# nrf24l01_shield.net
KiCad netlist of a schematic drawn in EAGLE
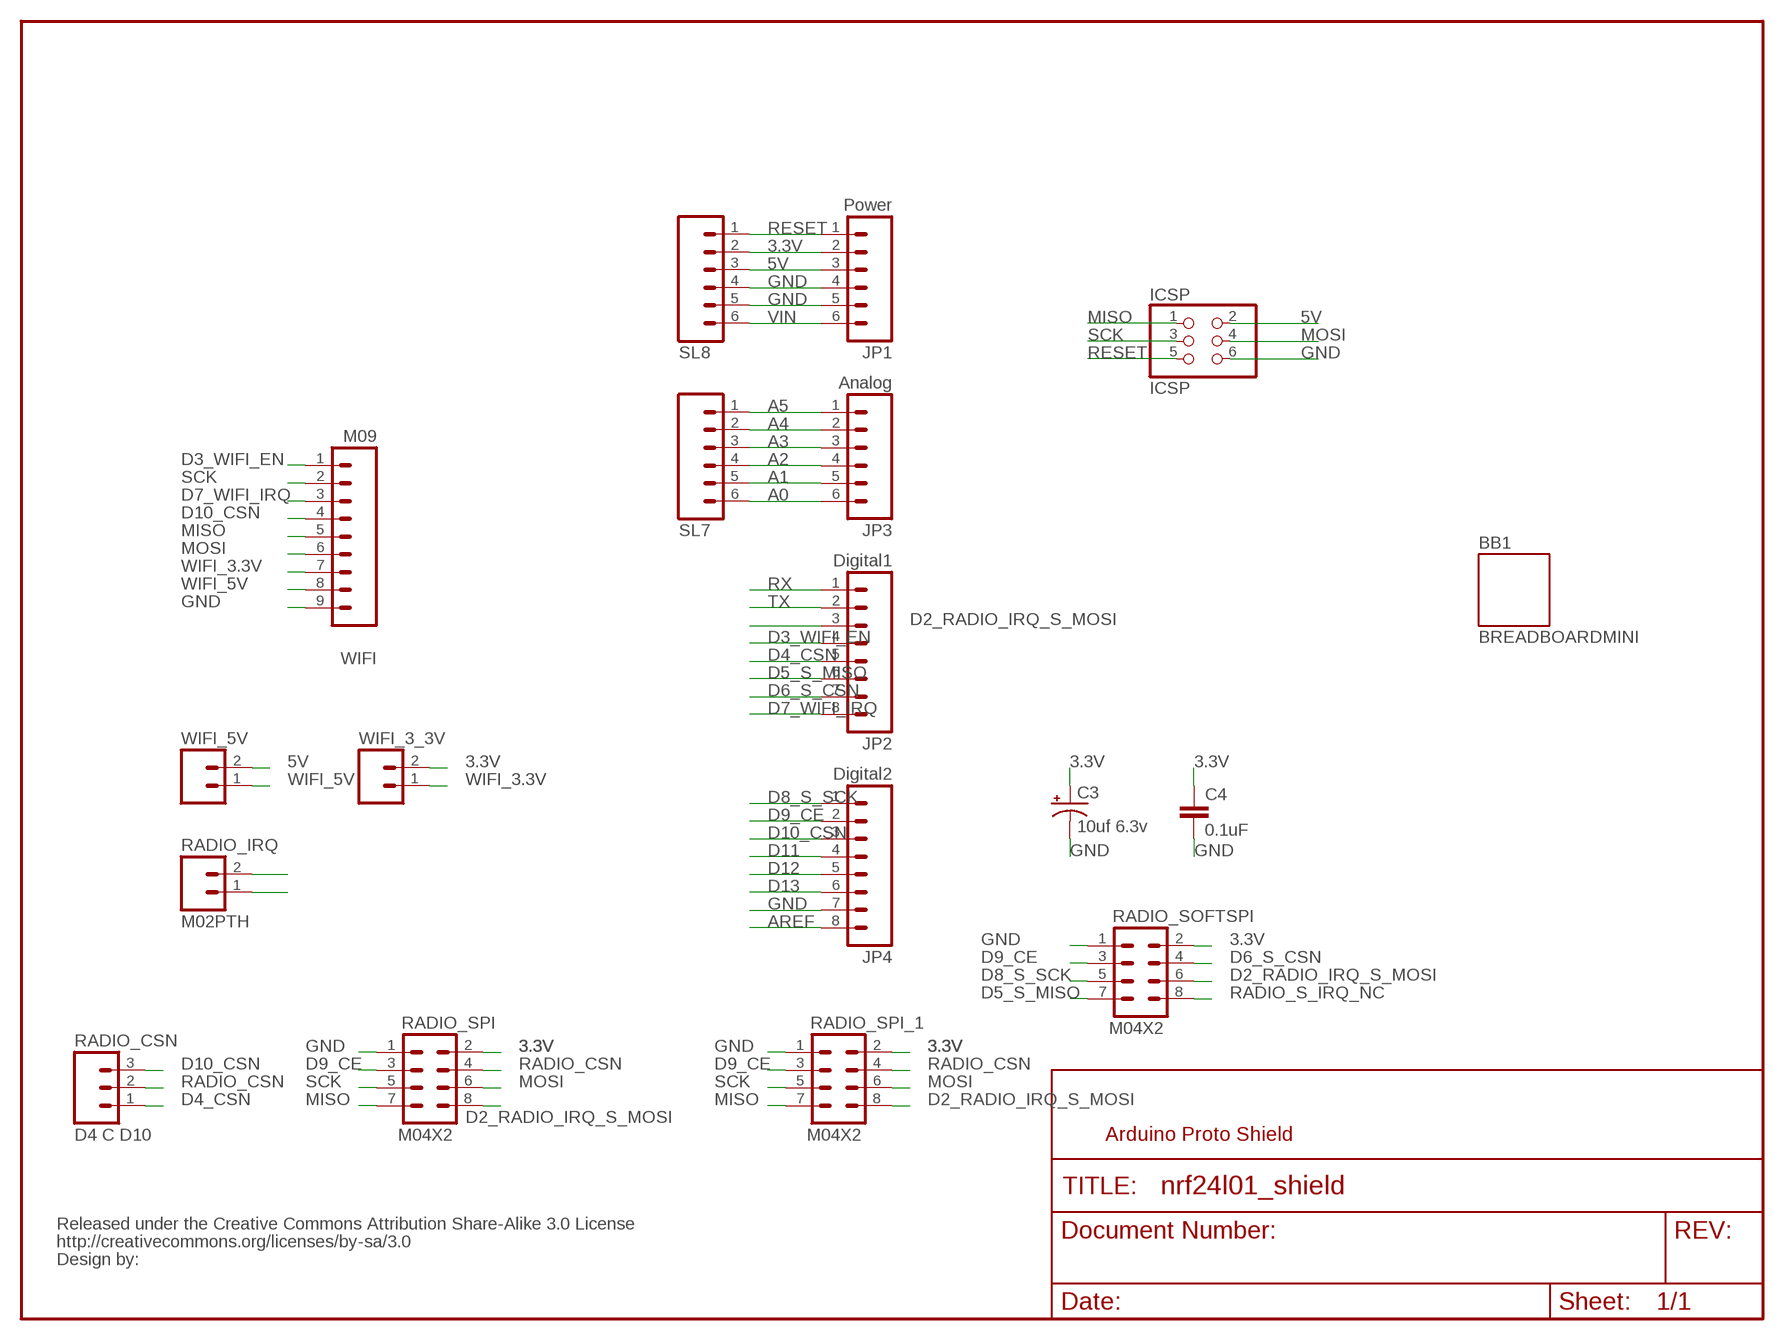
[diagram p0: schematic, sheet 1]

(export (version "E")
  (design (tool "Eeschema 10.0.6"))
  (components
    (comp (ref "BB1")
      (value "BREADBOARDMINI")
      (footprint "eagle-import:BREADBOARD-MINI")
      (libsource (lib "eagle-import") (part "BREADBOARDMINI"))
    )
    (comp (ref "C3")
      (value "10uf 6.3v")
      (footprint "eagle-import:CPOL-RADIAL-10UF-25V")
      (libsource (lib "eagle-import") (part "CAP_POLPTH2"))
    )
    (comp (ref "C4")
      (value "0.1uF")
      (footprint "eagle-import:CAP-PTH-SMALL2")
      (libsource (lib "eagle-import") (part "CAPPTH2"))
    )
    (comp (ref "ICSP")
      (value "ICSP")
      (footprint "eagle-import:2X03")
      (libsource (lib "eagle-import") (part "PINHD-2X3"))
    )
    (comp (ref "JP1")
      (value "Power")
      (footprint "eagle-import:1X06")
      (libsource (lib "eagle-import") (part "M06SIP"))
    )
    (comp (ref "JP2")
      (value "Digital1")
      (footprint "eagle-import:1X08")
      (libsource (lib "eagle-import") (part "M08"))
    )
    (comp (ref "JP3")
      (value "Analog")
      (footprint "eagle-import:1X06")
      (libsource (lib "eagle-import") (part "M06SIP"))
    )
    (comp (ref "JP4")
      (value "Digital2")
      (footprint "eagle-import:1X08")
      (libsource (lib "eagle-import") (part "M08"))
    )
    (comp (ref "RADIO_CSN")
      (value "D4 C D10")
      (footprint "eagle-import:1X03")
      (libsource (lib "eagle-import") (part "M03PTH"))
    )
    (comp (ref "RADIO_IRQ")
      (value "M02PTH")
      (footprint "eagle-import:1X02")
      (libsource (lib "eagle-import") (part "M02PTH"))
    )
    (comp (ref "RADIO_SOFTSPI")
      (value "M04X2")
      (footprint "eagle-import:2X4")
      (libsource (lib "eagle-import") (part "M04X2"))
    )
    (comp (ref "RADIO_SPI")
      (value "M04X2")
      (footprint "eagle-import:2X4")
      (libsource (lib "eagle-import") (part "M04X2"))
    )
    (comp (ref "RADIO_SPI_1")
      (value "M04X2")
      (footprint "eagle-import:2X4")
      (libsource (lib "eagle-import") (part "M04X2"))
    )
    (comp (ref "SL7")
      (value "M06SIP")
      (footprint "eagle-import:1X06")
      (libsource (lib "eagle-import") (part "M06SIP"))
    )
    (comp (ref "SL8")
      (value "M06SIP")
      (footprint "eagle-import:1X06")
      (libsource (lib "eagle-import") (part "M06SIP"))
    )
    (comp (ref "U$2")
      (value "CREATIVE_COMMONS")
      (footprint "eagle-import:CREATIVE_COMMONS")
      (libsource (lib "eagle-import") (part "CREATIVE_COMMONS"))
    )
    (comp (ref "WIFI")
      (value "M09")
      (footprint "eagle-import:1X09")
      (libsource (lib "eagle-import") (part "M09"))
    )
    (comp (ref "WIFI_3_3V")
      (value "M02PTH")
      (footprint "eagle-import:1X02")
      (libsource (lib "eagle-import") (part "M02PTH"))
    )
    (comp (ref "WIFI_5V")
      (value "M02PTH")
      (footprint "eagle-import:1X02")
      (libsource (lib "eagle-import") (part "M02PTH"))
    )
  )
  (nets
    (net (code "1") (name "/3.3V") (class "Default")
      (node (ref "C3") (pin "1") (pinfunction "+_1") (pintype "passive"))
      (node (ref "C4") (pin "1") (pinfunction "1_1") (pintype "passive"))
      (node (ref "JP1") (pin "2") (pinfunction "2_2") (pintype "passive"))
      (node (ref "RADIO_SOFTSPI") (pin "2") (pinfunction "2_2") (pintype "passive"))
      (node (ref "RADIO_SPI") (pin "2") (pinfunction "2_2") (pintype "passive"))
      (node (ref "RADIO_SPI_1") (pin "2") (pinfunction "2_2") (pintype "passive"))
      (node (ref "SL8") (pin "2") (pinfunction "2_2") (pintype "passive"))
      (node (ref "WIFI_3_3V") (pin "2") (pinfunction "2_2") (pintype "passive"))
    )
    (net (code "2") (name "/5V") (class "Default")
      (node (ref "ICSP") (pin "2") (pinfunction "2_2") (pintype "passive"))
      (node (ref "JP1") (pin "3") (pinfunction "3_3") (pintype "passive"))
      (node (ref "SL8") (pin "3") (pinfunction "3_3") (pintype "passive"))
      (node (ref "WIFI_5V") (pin "2") (pinfunction "2_2") (pintype "passive"))
    )
    (net (code "3") (name "/A0") (class "Default")
      (node (ref "JP3") (pin "6") (pinfunction "6_6") (pintype "passive"))
      (node (ref "SL7") (pin "6") (pinfunction "6_6") (pintype "passive"))
    )
    (net (code "4") (name "/A1") (class "Default")
      (node (ref "JP3") (pin "5") (pinfunction "5_5") (pintype "passive"))
      (node (ref "SL7") (pin "5") (pinfunction "5_5") (pintype "passive"))
    )
    (net (code "5") (name "/A2") (class "Default")
      (node (ref "JP3") (pin "4") (pinfunction "4_4") (pintype "passive"))
      (node (ref "SL7") (pin "4") (pinfunction "4_4") (pintype "passive"))
    )
    (net (code "6") (name "/A3") (class "Default")
      (node (ref "JP3") (pin "3") (pinfunction "3_3") (pintype "passive"))
      (node (ref "SL7") (pin "3") (pinfunction "3_3") (pintype "passive"))
    )
    (net (code "7") (name "/A4") (class "Default")
      (node (ref "JP3") (pin "2") (pinfunction "2_2") (pintype "passive"))
      (node (ref "SL7") (pin "2") (pinfunction "2_2") (pintype "passive"))
    )
    (net (code "8") (name "/A5") (class "Default")
      (node (ref "JP3") (pin "1") (pinfunction "1_1") (pintype "passive"))
      (node (ref "SL7") (pin "1") (pinfunction "1_1") (pintype "passive"))
    )
    (net (code "9") (name "/AREF") (class "Default")
      (node (ref "JP4") (pin "8") (pinfunction "8_8") (pintype "passive"))
    )
    (net (code "10") (name "/D2_RADIO_IRQ_S_MOSI") (class "Default")
      (node (ref "JP2") (pin "3") (pinfunction "3_3") (pintype "passive"))
      (node (ref "RADIO_SOFTSPI") (pin "6") (pinfunction "6_6") (pintype "passive"))
      (node (ref "RADIO_SPI") (pin "8") (pinfunction "8_8") (pintype "passive"))
      (node (ref "RADIO_SPI_1") (pin "8") (pinfunction "8_8") (pintype "passive"))
    )
    (net (code "11") (name "/D3_WIFI_EN") (class "Default")
      (node (ref "JP2") (pin "4") (pinfunction "4_4") (pintype "passive"))
      (node (ref "WIFI") (pin "1") (pinfunction "1_1") (pintype "passive"))
    )
    (net (code "12") (name "/D4_CSN") (class "Default")
      (node (ref "JP2") (pin "5") (pinfunction "5_5") (pintype "passive"))
      (node (ref "RADIO_CSN") (pin "1") (pinfunction "1_1") (pintype "passive"))
    )
    (net (code "13") (name "/D5_S_MISO") (class "Default")
      (node (ref "JP2") (pin "6") (pinfunction "6_6") (pintype "passive"))
      (node (ref "RADIO_SOFTSPI") (pin "7") (pinfunction "7_7") (pintype "passive"))
    )
    (net (code "14") (name "/D6_S_CSN") (class "Default")
      (node (ref "JP2") (pin "7") (pinfunction "7_7") (pintype "passive"))
      (node (ref "RADIO_SOFTSPI") (pin "4") (pinfunction "4_4") (pintype "passive"))
    )
    (net (code "15") (name "/D7_WIFI_IRQ") (class "Default")
      (node (ref "JP2") (pin "8") (pinfunction "8_8") (pintype "passive"))
      (node (ref "WIFI") (pin "3") (pinfunction "3_3") (pintype "passive"))
    )
    (net (code "16") (name "/D8_S_SCK") (class "Default")
      (node (ref "JP4") (pin "1") (pinfunction "1_1") (pintype "passive"))
      (node (ref "RADIO_SOFTSPI") (pin "5") (pinfunction "5_5") (pintype "passive"))
    )
    (net (code "17") (name "/D9_CE") (class "Default")
      (node (ref "JP4") (pin "2") (pinfunction "2_2") (pintype "passive"))
      (node (ref "RADIO_SOFTSPI") (pin "3") (pinfunction "3_3") (pintype "passive"))
      (node (ref "RADIO_SPI") (pin "3") (pinfunction "3_3") (pintype "passive"))
      (node (ref "RADIO_SPI_1") (pin "3") (pinfunction "3_3") (pintype "passive"))
    )
    (net (code "18") (name "/D10_CSN") (class "Default")
      (node (ref "JP4") (pin "3") (pinfunction "3_3") (pintype "passive"))
      (node (ref "RADIO_CSN") (pin "3") (pinfunction "3_3") (pintype "passive"))
      (node (ref "WIFI") (pin "4") (pinfunction "4_4") (pintype "passive"))
    )
    (net (code "19") (name "/D11") (class "Default")
      (node (ref "JP4") (pin "4") (pinfunction "4_4") (pintype "passive"))
    )
    (net (code "20") (name "/D12") (class "Default")
      (node (ref "JP4") (pin "5") (pinfunction "5_5") (pintype "passive"))
    )
    (net (code "21") (name "/D13") (class "Default")
      (node (ref "JP4") (pin "6") (pinfunction "6_6") (pintype "passive"))
    )
    (net (code "22") (name "/GND") (class "Default")
      (node (ref "C3") (pin "2") (pinfunction "-_2") (pintype "passive"))
      (node (ref "C4") (pin "2") (pinfunction "2_2") (pintype "passive"))
      (node (ref "ICSP") (pin "6") (pinfunction "6_6") (pintype "passive"))
      (node (ref "JP1") (pin "4") (pinfunction "4_4") (pintype "passive"))
      (node (ref "JP1") (pin "5") (pinfunction "5_5") (pintype "passive"))
      (node (ref "JP4") (pin "7") (pinfunction "7_7") (pintype "passive"))
      (node (ref "RADIO_SOFTSPI") (pin "1") (pinfunction "1_1") (pintype "passive"))
      (node (ref "RADIO_SPI") (pin "1") (pinfunction "1_1") (pintype "passive"))
      (node (ref "RADIO_SPI_1") (pin "1") (pinfunction "1_1") (pintype "passive"))
      (node (ref "SL8") (pin "4") (pinfunction "4_4") (pintype "passive"))
      (node (ref "SL8") (pin "5") (pinfunction "5_5") (pintype "passive"))
      (node (ref "WIFI") (pin "9") (pinfunction "9_9") (pintype "passive"))
    )
    (net (code "23") (name "/MISO") (class "Default")
      (node (ref "ICSP") (pin "1") (pinfunction "1_1") (pintype "passive"))
      (node (ref "RADIO_SPI") (pin "7") (pinfunction "7_7") (pintype "passive"))
      (node (ref "RADIO_SPI_1") (pin "7") (pinfunction "7_7") (pintype "passive"))
      (node (ref "WIFI") (pin "5") (pinfunction "5_5") (pintype "passive"))
    )
    (net (code "24") (name "/MOSI") (class "Default")
      (node (ref "ICSP") (pin "4") (pinfunction "4_4") (pintype "passive"))
      (node (ref "RADIO_SPI") (pin "6") (pinfunction "6_6") (pintype "passive"))
      (node (ref "RADIO_SPI_1") (pin "6") (pinfunction "6_6") (pintype "passive"))
      (node (ref "WIFI") (pin "6") (pinfunction "6_6") (pintype "passive"))
    )
    (net (code "25") (name "/RADIO_CSN") (class "Default")
      (node (ref "RADIO_CSN") (pin "2") (pinfunction "2_2") (pintype "passive"))
      (node (ref "RADIO_SPI") (pin "4") (pinfunction "4_4") (pintype "passive"))
      (node (ref "RADIO_SPI_1") (pin "4") (pinfunction "4_4") (pintype "passive"))
    )
    (net (code "26") (name "/RADIO_S_IRQ_NC") (class "Default")
      (node (ref "RADIO_SOFTSPI") (pin "8") (pinfunction "8_8") (pintype "passive"))
    )
    (net (code "27") (name "/RESET") (class "Default")
      (node (ref "ICSP") (pin "5") (pinfunction "5_5") (pintype "passive"))
      (node (ref "JP1") (pin "1") (pinfunction "1_1") (pintype "passive"))
      (node (ref "SL8") (pin "1") (pinfunction "1_1") (pintype "passive"))
    )
    (net (code "28") (name "/RX") (class "Default")
      (node (ref "JP2") (pin "1") (pinfunction "1_1") (pintype "passive"))
    )
    (net (code "29") (name "/SCK") (class "Default")
      (node (ref "ICSP") (pin "3") (pinfunction "3_3") (pintype "passive"))
      (node (ref "RADIO_SPI") (pin "5") (pinfunction "5_5") (pintype "passive"))
      (node (ref "RADIO_SPI_1") (pin "5") (pinfunction "5_5") (pintype "passive"))
      (node (ref "WIFI") (pin "2") (pinfunction "2_2") (pintype "passive"))
    )
    (net (code "30") (name "/TX") (class "Default")
      (node (ref "JP2") (pin "2") (pinfunction "2_2") (pintype "passive"))
    )
    (net (code "31") (name "/VIN") (class "Default")
      (node (ref "JP1") (pin "6") (pinfunction "6_6") (pintype "passive"))
      (node (ref "SL8") (pin "6") (pinfunction "6_6") (pintype "passive"))
    )
    (net (code "32") (name "/WIFI_3.3V") (class "Default")
      (node (ref "WIFI") (pin "7") (pinfunction "7_7") (pintype "passive"))
      (node (ref "WIFI_3_3V") (pin "1") (pinfunction "1_1") (pintype "passive"))
    )
    (net (code "33") (name "/WIFI_5V") (class "Default")
      (node (ref "WIFI") (pin "8") (pinfunction "8_8") (pintype "passive"))
      (node (ref "WIFI_5V") (pin "1") (pinfunction "1_1") (pintype "passive"))
    )
    (net (code "34") (name "unconnected-(RADIO_IRQ-Pad1)") (class "Default")
      (node (ref "RADIO_IRQ") (pin "1") (pinfunction "1_1") (pintype "passive"))
    )
    (net (code "35") (name "unconnected-(RADIO_IRQ-Pad2)") (class "Default")
      (node (ref "RADIO_IRQ") (pin "2") (pinfunction "2_2") (pintype "passive"))
    )
  )
)
